# Power_Board_3.net
KiCad netlist of a schematic drawn in Altium Designer
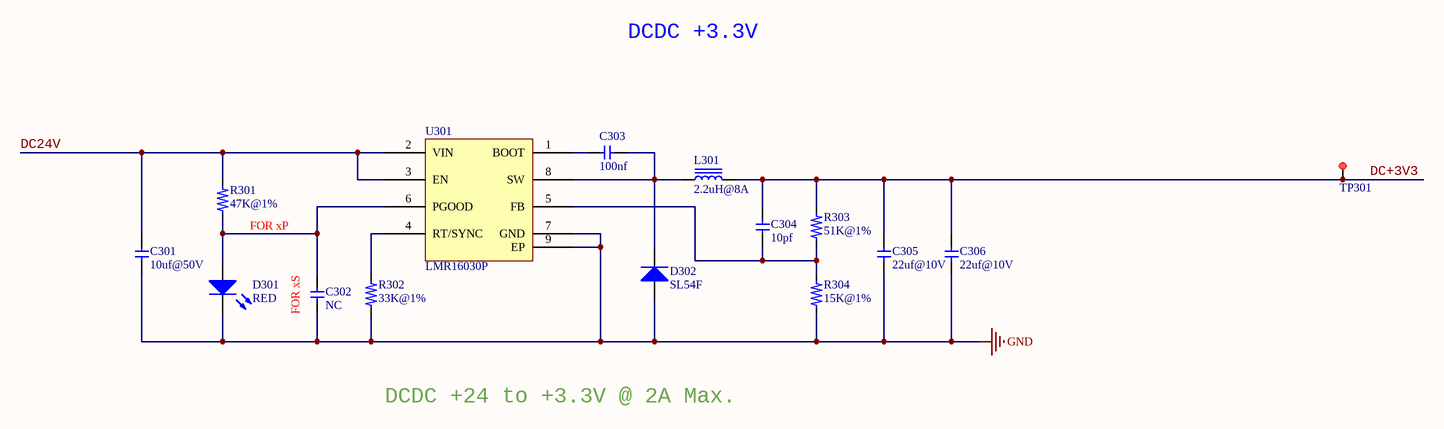
[diagram p0: Power Board.3.SchDoc]

(export (version "E")
  (design (tool "Eeschema 10.0.6"))
  (components
    (comp (ref "C301")
      (value "10uf@50V")
      (footprint "C1206")
      (fields (field (name "Comment") "Cap"))
      (libsource (lib "carrot_lib") (part "Cap"))
    )
    (comp (ref "C302")
      (value "NC")
      (footprint "C0603")
      (fields (field (name "Comment") "Cap"))
      (libsource (lib "carrot_lib") (part "Cap"))
    )
    (comp (ref "C303")
      (value "100nf")
      (footprint "C0603")
      (fields (field (name "Comment") "Cap"))
      (libsource (lib "carrot_lib") (part "Cap"))
    )
    (comp (ref "C304")
      (value "10pf")
      (footprint "C0603")
      (fields (field (name "Comment") "Cap"))
      (libsource (lib "carrot_lib") (part "Cap"))
    )
    (comp (ref "C305")
      (value "22uf@10V")
      (footprint "C1206")
      (fields (field (name "Comment") "Cap"))
      (libsource (lib "carrot_lib") (part "Cap"))
    )
    (comp (ref "C306")
      (value "22uf@10V")
      (footprint "C1206")
      (fields (field (name "Comment") "Cap"))
      (libsource (lib "carrot_lib") (part "Cap"))
    )
    (comp (ref "D301")
      (value "RED")
      (footprint "LED0603")
      (fields (field (name "Comment") "LED"))
      (libsource (lib "carrot_lib") (part "LED"))
    )
    (comp (ref "D302")
      (value "SL54F")
      (footprint "DIODE-SMAF")
      (description "通用二极管")
      (fields (field (name "Comment") "Diode"))
      (libsource (lib "carrot_lib") (part "Diode"))
    )
    (comp (ref "L301")
      (value "2.2uH@8A")
      (footprint "L06063")
      (description "Magnetic-Core Inductor")
      (fields (field (name "Comment") "Inductor Iron"))
      (libsource (lib "carrot_lib") (part "Inductor Iron"))
    )
    (comp (ref "R301")
      (value "47K@1%")
      (footprint "R0603")
      (description "电阻")
      (fields (field (name "Comment") "Res"))
      (libsource (lib "carrot_lib") (part "Res"))
    )
    (comp (ref "R302")
      (value "33K@1%")
      (footprint "R0603")
      (description "电阻")
      (fields (field (name "Comment") "Res"))
      (libsource (lib "carrot_lib") (part "Res"))
    )
    (comp (ref "R303")
      (value "51K@1%")
      (footprint "R0603")
      (description "电阻")
      (fields (field (name "Comment") "Res"))
      (libsource (lib "carrot_lib") (part "Res"))
    )
    (comp (ref "R304")
      (value "15K@1%")
      (footprint "R0603")
      (description "电阻")
      (fields (field (name "Comment") "Res"))
      (libsource (lib "carrot_lib") (part "Res"))
    )
    (comp (ref "TP301")
      (value "TestPoint")
      (footprint "TestPoint-SMD100")
      (description "测试点")
      (libsource (lib "carrot_lib") (part "TestPoint"))
    )
    (comp (ref "U301")
      (value "LMR16030P")
      (footprint "LMR16030-SOIC8")
      (description "LMR16030 SIMPLE SWITCHER® 60-V, 3-A Step-Down Converter With 40-µA IQ")
      (libsource (lib "carrot_lib") (part "LMR16030P"))
    )
  )
  (nets
    (net (code "1") (name "/DC+3V3") (class "Default")
      (node (ref "C304") (pin "1") (pinfunction "1_1") (pintype "passive"))
      (node (ref "C305") (pin "2") (pinfunction "2_2") (pintype "passive"))
      (node (ref "C306") (pin "2") (pinfunction "2_2") (pintype "passive"))
      (node (ref "L301") (pin "2") (pinfunction "2_2") (pintype "passive"))
      (node (ref "R303") (pin "2") (pinfunction "2_2") (pintype "passive"))
      (node (ref "TP301") (pin "1") (pinfunction "1_1") (pintype "passive"))
    )
    (net (code "2") (name "/DC24V") (class "Default")
      (node (ref "C301") (pin "2") (pinfunction "2_2") (pintype "passive"))
      (node (ref "R301") (pin "2") (pinfunction "2_2") (pintype "passive"))
      (node (ref "U301") (pin "2") (pinfunction "VIN_2") (pintype "passive"))
      (node (ref "U301") (pin "3") (pinfunction "EN_3") (pintype "passive"))
    )
    (net (code "3") (name "GND") (class "Default")
      (node (ref "C301") (pin "1") (pinfunction "1_1") (pintype "passive"))
      (node (ref "C302") (pin "1") (pinfunction "1_1") (pintype "passive"))
      (node (ref "C305") (pin "1") (pinfunction "1_1") (pintype "passive"))
      (node (ref "C306") (pin "1") (pinfunction "1_1") (pintype "passive"))
      (node (ref "D301") (pin "2") (pinfunction "K_2") (pintype "passive"))
      (node (ref "D302") (pin "1") (pinfunction "A_1") (pintype "passive"))
      (node (ref "R302") (pin "1") (pinfunction "1_1") (pintype "passive"))
      (node (ref "R304") (pin "1") (pinfunction "1_1") (pintype "passive"))
      (node (ref "U301") (pin "7") (pinfunction "GND_7") (pintype "passive"))
      (node (ref "U301") (pin "9") (pinfunction "EP_9") (pintype "passive"))
    )
    (net (code "4") (name "Net-(D301-A)") (class "Default")
      (node (ref "C302") (pin "2") (pinfunction "2_2") (pintype "passive"))
      (node (ref "D301") (pin "1") (pinfunction "A_1") (pintype "passive"))
      (node (ref "R301") (pin "1") (pinfunction "1_1") (pintype "passive"))
      (node (ref "U301") (pin "6") (pinfunction "PGOOD_6") (pintype "passive"))
    )
    (net (code "5") (name "Net-(D302-K)") (class "Default")
      (node (ref "C303") (pin "1") (pinfunction "1_1") (pintype "passive"))
      (node (ref "D302") (pin "2") (pinfunction "K_2") (pintype "passive"))
      (node (ref "L301") (pin "1") (pinfunction "1_1") (pintype "passive"))
      (node (ref "U301") (pin "8") (pinfunction "SW_8") (pintype "passive"))
    )
    (net (code "6") (name "Net-(U301-BOOT)") (class "Default")
      (node (ref "C303") (pin "2") (pinfunction "2_2") (pintype "passive"))
      (node (ref "U301") (pin "1") (pinfunction "BOOT_1") (pintype "passive"))
    )
    (net (code "7") (name "Net-(U301-FB)") (class "Default")
      (node (ref "C304") (pin "2") (pinfunction "2_2") (pintype "passive"))
      (node (ref "R303") (pin "1") (pinfunction "1_1") (pintype "passive"))
      (node (ref "R304") (pin "2") (pinfunction "2_2") (pintype "passive"))
      (node (ref "U301") (pin "5") (pinfunction "FB_5") (pintype "passive"))
    )
    (net (code "8") (name "Net-(U301-RT{slash}SYNC)") (class "Default")
      (node (ref "R302") (pin "2") (pinfunction "2_2") (pintype "passive"))
      (node (ref "U301") (pin "4") (pinfunction "RT/SYNC_4") (pintype "passive"))
    )
  )
)
